# CHARGING_IC.net
KiCad netlist of a schematic drawn in Altium Designer
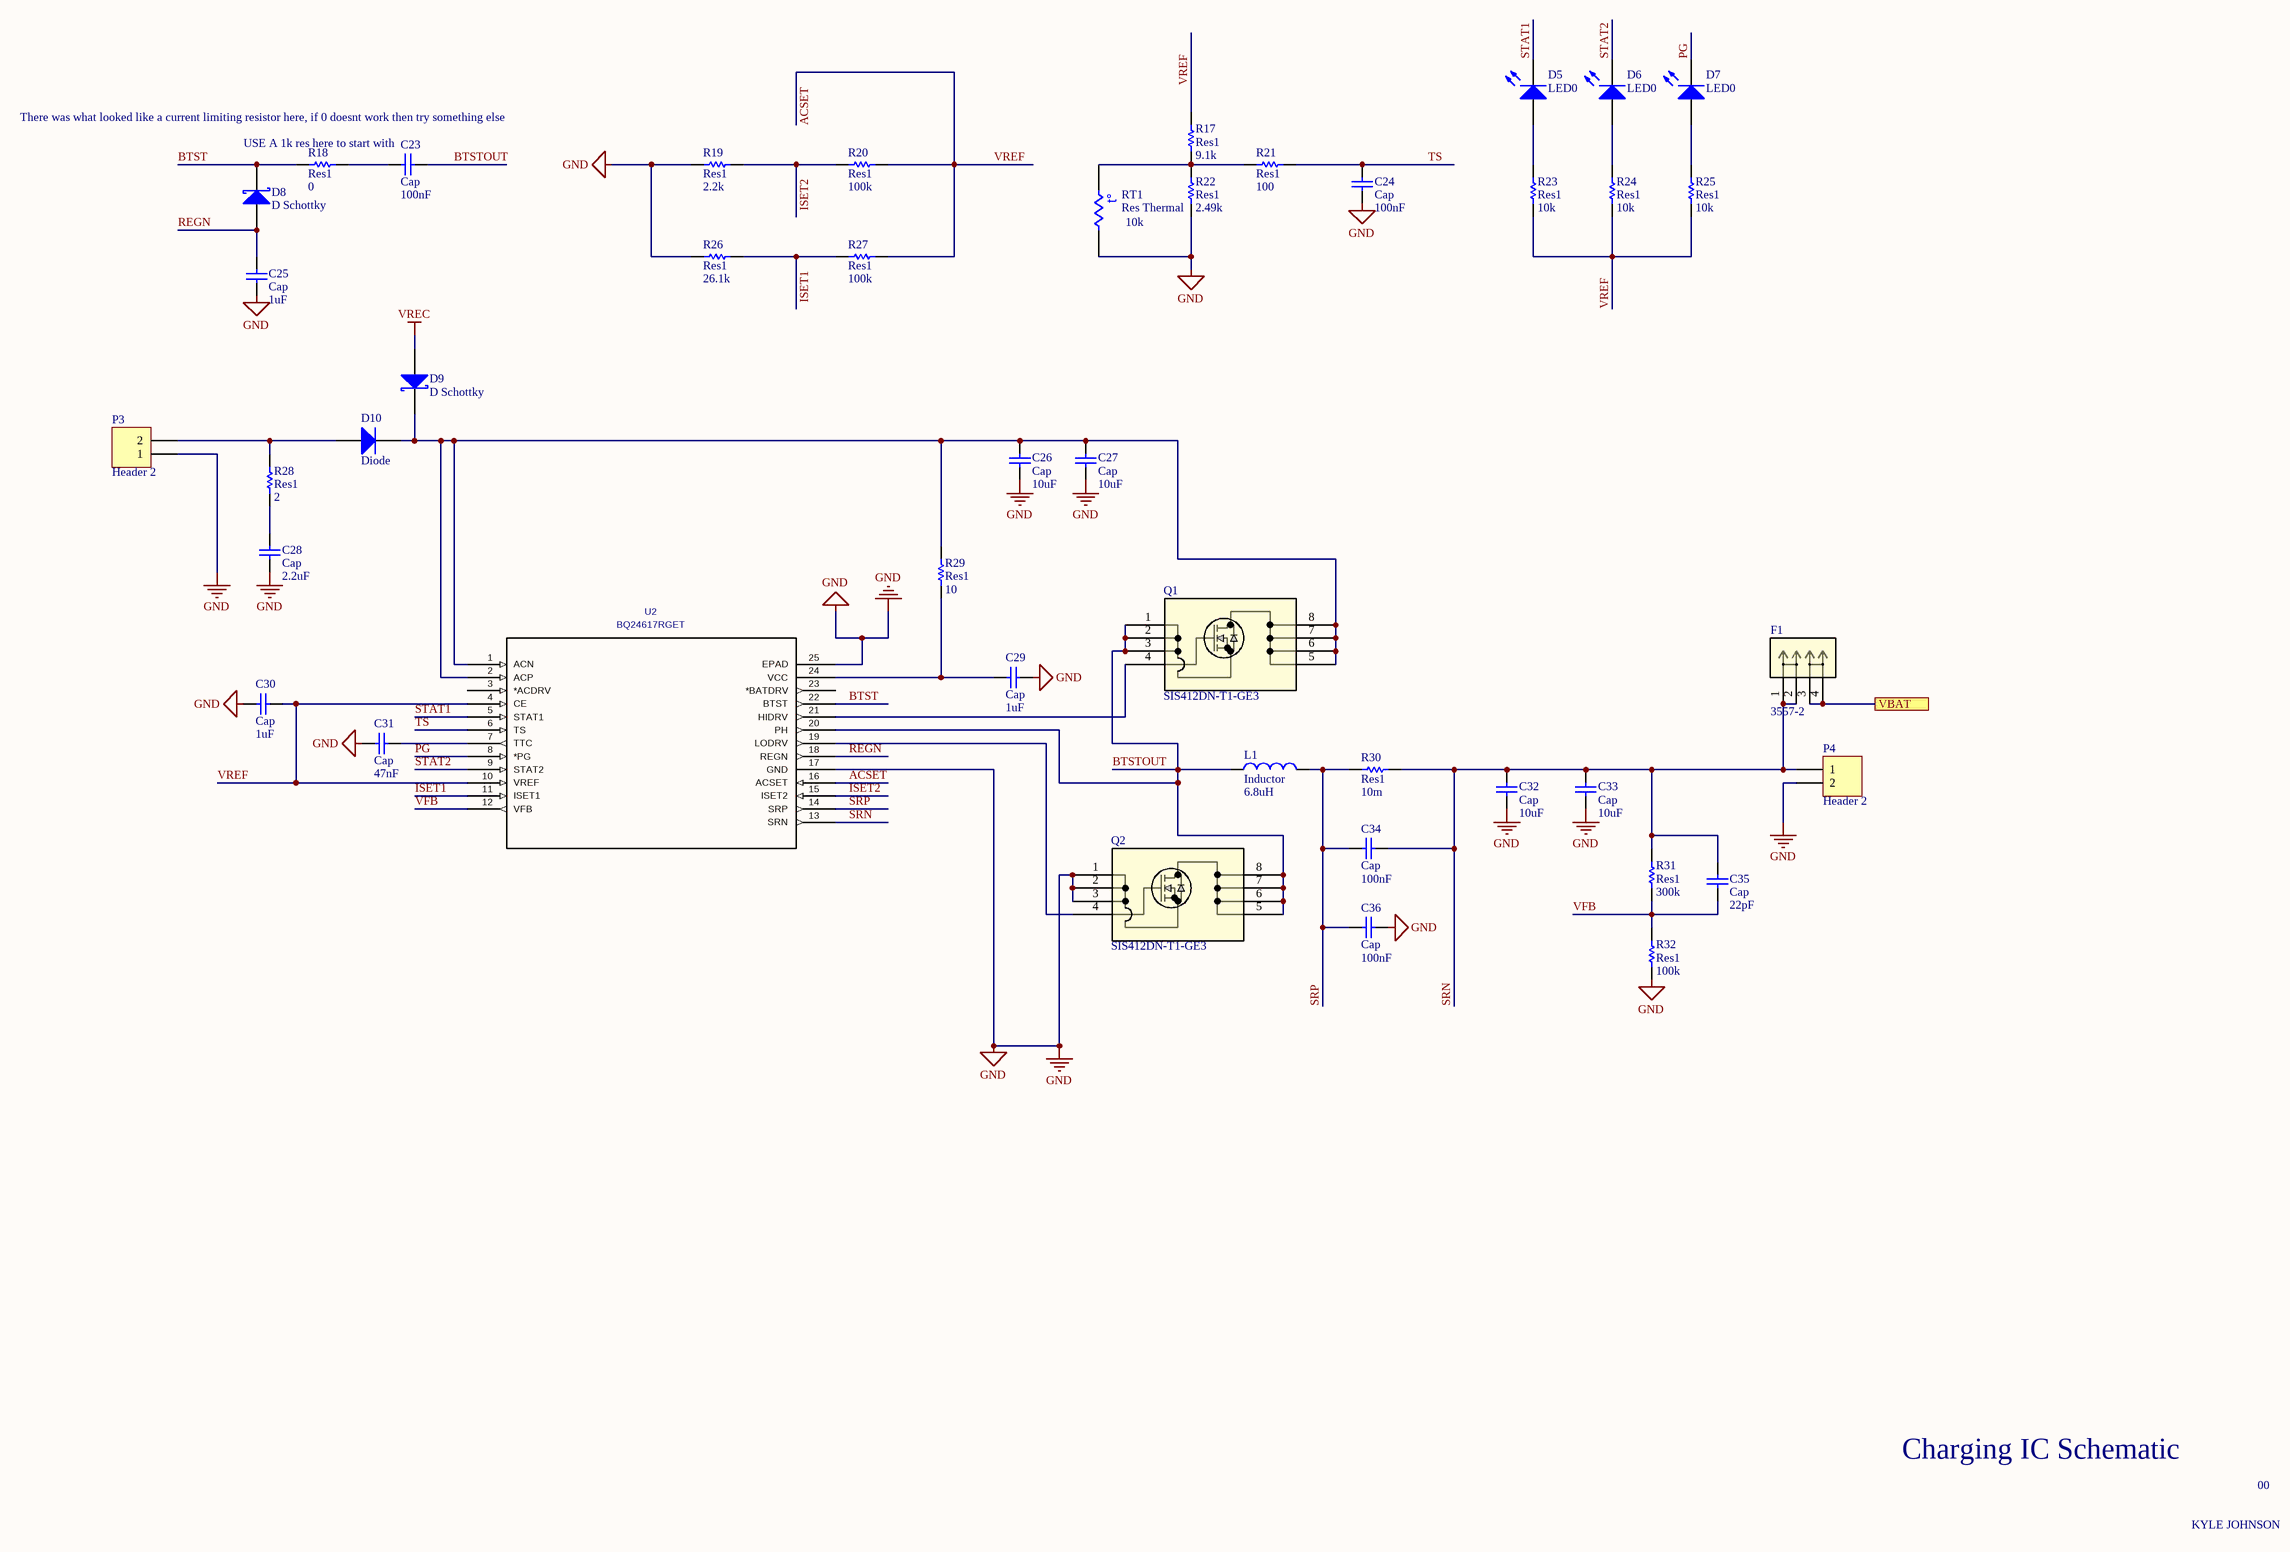
[diagram p0: CHARGING IC.SchDoc]

(export (version "E")
  (design (tool "Eeschema 10.0.6"))
  (components
    (comp (ref "C23")
      (value "Cap")
      (footprint "0402-A")
      (description "Capacitor")
      (fields (field (name "ALTIUM_VALUE") "100nF") (field (name "PUBLISHER") "Altium Limited"))
      (libsource (lib "Miscellaneous Devices") (part "Cap"))
    )
    (comp (ref "C24")
      (value "Cap")
      (footprint "0402-A")
      (description "Capacitor")
      (fields (field (name "ALTIUM_VALUE") "100nF") (field (name "PUBLISHER") "Altium Limited"))
      (libsource (lib "Miscellaneous Devices") (part "Cap"))
    )
    (comp (ref "C25")
      (value "Cap")
      (footprint "0402-A")
      (description "Capacitor")
      (fields (field (name "ALTIUM_VALUE") "1uF") (field (name "PUBLISHER") "Altium Limited"))
      (libsource (lib "Miscellaneous Devices") (part "Cap"))
    )
    (comp (ref "C26")
      (value "Cap")
      (footprint "6-0805_M")
      (description "Capacitor")
      (fields (field (name "ALTIUM_VALUE") "10uF") (field (name "PUBLISHER") "Altium Limited"))
      (libsource (lib "Miscellaneous Devices") (part "Cap"))
    )
    (comp (ref "C27")
      (value "Cap")
      (footprint "6-0805_M")
      (description "Capacitor")
      (fields (field (name "ALTIUM_VALUE") "10uF") (field (name "PUBLISHER") "Altium Limited"))
      (libsource (lib "Miscellaneous Devices") (part "Cap"))
    )
    (comp (ref "C28")
      (value "Cap")
      (footprint "1608[0603]")
      (description "Capacitor")
      (fields (field (name "ALTIUM_VALUE") "2.2uF") (field (name "PUBLISHER") "Altium Limited"))
      (libsource (lib "Miscellaneous Devices") (part "Cap"))
    )
    (comp (ref "C29")
      (value "Cap")
      (footprint "0402-A")
      (description "Capacitor")
      (fields (field (name "ALTIUM_VALUE") "1uF") (field (name "PUBLISHER") "Altium Limited"))
      (libsource (lib "Miscellaneous Devices") (part "Cap"))
    )
    (comp (ref "C30")
      (value "Cap")
      (footprint "0402-A")
      (description "Capacitor")
      (fields (field (name "ALTIUM_VALUE") "1uF") (field (name "PUBLISHER") "Altium Limited"))
      (libsource (lib "Miscellaneous Devices") (part "Cap"))
    )
    (comp (ref "C31")
      (value "Cap")
      (footprint "0402-A")
      (description "Capacitor")
      (fields (field (name "ALTIUM_VALUE") "47nF") (field (name "PUBLISHER") "Altium Limited"))
      (libsource (lib "Miscellaneous Devices") (part "Cap"))
    )
    (comp (ref "C32")
      (value "Cap")
      (footprint "6-0805_M")
      (description "Capacitor")
      (fields (field (name "ALTIUM_VALUE") "10uF") (field (name "PUBLISHER") "Altium Limited"))
      (libsource (lib "Miscellaneous Devices") (part "Cap"))
    )
    (comp (ref "C33")
      (value "Cap")
      (footprint "6-0805_M")
      (description "Capacitor")
      (fields (field (name "ALTIUM_VALUE") "10uF") (field (name "PUBLISHER") "Altium Limited"))
      (libsource (lib "Miscellaneous Devices") (part "Cap"))
    )
    (comp (ref "C34")
      (value "Cap")
      (footprint "0402-A")
      (description "Capacitor")
      (fields (field (name "ALTIUM_VALUE") "100nF") (field (name "PUBLISHER") "Altium Limited"))
      (libsource (lib "Miscellaneous Devices") (part "Cap"))
    )
    (comp (ref "C35")
      (value "Cap")
      (footprint "0402-A")
      (description "Capacitor")
      (fields (field (name "ALTIUM_VALUE") "22pF") (field (name "PUBLISHER") "Altium Limited"))
      (libsource (lib "Miscellaneous Devices") (part "Cap"))
    )
    (comp (ref "C36")
      (value "Cap")
      (footprint "0402-A")
      (description "Capacitor")
      (fields (field (name "ALTIUM_VALUE") "100nF") (field (name "PUBLISHER") "Altium Limited"))
      (libsource (lib "Miscellaneous Devices") (part "Cap"))
    )
    (comp (ref "D5")
      (value "LED0")
      (footprint "1608[0603]")
      (fields (field (name "PUBLISHER") "Altium Limited"))
      (libsource (lib "Miscellaneous Devices") (part "LED0"))
    )
    (comp (ref "D6")
      (value "LED0")
      (footprint "1608[0603]")
      (fields (field (name "PUBLISHER") "Altium Limited"))
      (libsource (lib "Miscellaneous Devices") (part "LED0"))
    )
    (comp (ref "D7")
      (value "LED0")
      (footprint "1608[0603]")
      (fields (field (name "PUBLISHER") "Altium Limited"))
      (libsource (lib "Miscellaneous Devices") (part "LED0"))
    )
    (comp (ref "D8")
      (value "D Schottky")
      (footprint "425")
      (description "Schottky Diode")
      (fields (field (name "PUBLISHER") "Altium Limited"))
      (libsource (lib "Miscellaneous Devices") (part "D Schottky"))
    )
    (comp (ref "D9")
      (value "D Schottky")
      (footprint "425")
      (description "Schottky Diode")
      (fields (field (name "PUBLISHER") "Altium Limited"))
      (libsource (lib "Miscellaneous Devices") (part "D Schottky"))
    )
    (comp (ref "D10")
      (value "Diode")
      (footprint "X3-WLB1608-2")
      (description "Default Diode")
      (fields (field (name "PUBLISHER") "Altium Limited"))
      (libsource (lib "Miscellaneous Devices") (part "Diode"))
    )
    (comp (ref "F1")
      (value "3557-2")
      (footprint "CONN_3557-2_KEY")
      (description "No Description Available")
      (fields (field (name "COPYRIGHT") "Copyright (C) 2018 Accelerated Designs. All rights reserved"))
      (libsource (lib "3557-2") (part "3557-2"))
    )
    (comp (ref "L1")
      (value "Inductor")
      (footprint "IHLP2525CZER6R8MA1")
      (fields (field (name "ALTIUM_VALUE") "6.8uH") (field (name "PUBLISHER") "Altium Limited"))
      (libsource (lib "Miscellaneous Devices") (part "Inductor"))
    )
    (comp (ref "P3")
      (value "Header 2")
      (footprint "2-1445096-2")
      (description "Header, 2-Pin")
      (fields (field (name "PUBLISHER") "Altium Limited"))
      (libsource (lib "") (part "Header 2_1"))
    )
    (comp (ref "P4")
      (value "Header 2")
      (footprint "2-1445096-2")
      (description "Header, 2-Pin")
      (fields (field (name "PUBLISHER") "Altium Limited"))
      (libsource (lib "Miscellaneous Connectors") (part "Header 2"))
    )
    (comp (ref "Q1")
      (value "SIS412DN-T1-GE3")
      (footprint "POWERPAK_1212-8")
      (description "No Description Available")
      (fields (field (name "COPYRIGHT") "Copyright (C) 2018 Accelerated Designs. All rights reserved"))
      (libsource (lib "SIS412DN-T1-GE3") (part "SIS412DN-T1-GE3"))
    )
    (comp (ref "Q2")
      (value "SIS412DN-T1-GE3")
      (footprint "POWERPAK_1212-8")
      (description "No Description Available")
      (fields (field (name "COPYRIGHT") "Copyright (C) 2018 Accelerated Designs. All rights reserved"))
      (libsource (lib "SIS412DN-T1-GE3") (part "SIS412DN-T1-GE3"))
    )
    (comp (ref "R17")
      (value "Res1")
      (footprint "0402-A")
      (description "Resistor")
      (fields (field (name "ALTIUM_VALUE") "9.1k") (field (name "PUBLISHER") "Altium Limited"))
      (libsource (lib "Miscellaneous Devices") (part "Res1"))
    )
    (comp (ref "R18")
      (value "Res1")
      (footprint "0402-A")
      (description "Resistor")
      (fields (field (name "ALTIUM_VALUE") "0") (field (name "PUBLISHER") "Altium Limited"))
      (libsource (lib "Miscellaneous Devices") (part "Res1"))
    )
    (comp (ref "R19")
      (value "Res1")
      (footprint "0402-A")
      (description "Resistor")
      (fields (field (name "ALTIUM_VALUE") "2.2k") (field (name "PUBLISHER") "Altium Limited"))
      (libsource (lib "Miscellaneous Devices") (part "Res1"))
    )
    (comp (ref "R20")
      (value "Res1")
      (footprint "0402-A")
      (description "Resistor")
      (fields (field (name "ALTIUM_VALUE") "100k") (field (name "PUBLISHER") "Altium Limited"))
      (libsource (lib "Miscellaneous Devices") (part "Res1"))
    )
    (comp (ref "R21")
      (value "Res1")
      (footprint "0402-A")
      (description "Resistor")
      (fields (field (name "ALTIUM_VALUE") "100") (field (name "PUBLISHER") "Altium Limited"))
      (libsource (lib "Miscellaneous Devices") (part "Res1"))
    )
    (comp (ref "R22")
      (value "Res1")
      (footprint "0402-A")
      (description "Resistor")
      (fields (field (name "ALTIUM_VALUE") "2.49k") (field (name "PUBLISHER") "Altium Limited"))
      (libsource (lib "Miscellaneous Devices") (part "Res1"))
    )
    (comp (ref "R23")
      (value "Res1")
      (footprint "0402-A")
      (description "Resistor")
      (fields (field (name "ALTIUM_VALUE") "10k") (field (name "PUBLISHER") "Altium Limited"))
      (libsource (lib "Miscellaneous Devices") (part "Res1"))
    )
    (comp (ref "R24")
      (value "Res1")
      (footprint "0402-A")
      (description "Resistor")
      (fields (field (name "ALTIUM_VALUE") "10k") (field (name "PUBLISHER") "Altium Limited"))
      (libsource (lib "Miscellaneous Devices") (part "Res1"))
    )
    (comp (ref "R25")
      (value "Res1")
      (footprint "0402-A")
      (description "Resistor")
      (fields (field (name "ALTIUM_VALUE") "10k") (field (name "PUBLISHER") "Altium Limited"))
      (libsource (lib "Miscellaneous Devices") (part "Res1"))
    )
    (comp (ref "R26")
      (value "Res1")
      (footprint "0402-A")
      (description "Resistor")
      (fields (field (name "ALTIUM_VALUE") "26.1k") (field (name "PUBLISHER") "Altium Limited"))
      (libsource (lib "Miscellaneous Devices") (part "Res1"))
    )
    (comp (ref "R27")
      (value "Res1")
      (footprint "0402-A")
      (description "Resistor")
      (fields (field (name "ALTIUM_VALUE") "100k") (field (name "PUBLISHER") "Altium Limited"))
      (libsource (lib "Miscellaneous Devices") (part "Res1"))
    )
    (comp (ref "R28")
      (value "Res1")
      (footprint "6-0805_M")
      (description "Resistor")
      (fields (field (name "ALTIUM_VALUE") "2") (field (name "PUBLISHER") "Altium Limited"))
      (libsource (lib "Miscellaneous Devices") (part "Res1"))
    )
    (comp (ref "R29")
      (value "Res1")
      (footprint "0402-A")
      (description "Resistor")
      (fields (field (name "ALTIUM_VALUE") "10") (field (name "PUBLISHER") "Altium Limited"))
      (libsource (lib "Miscellaneous Devices") (part "Res1"))
    )
    (comp (ref "R30")
      (value "Res1")
      (footprint "6-0805_M")
      (description "Resistor")
      (fields (field (name "ALTIUM_VALUE") "10m") (field (name "PUBLISHER") "Altium Limited"))
      (libsource (lib "Miscellaneous Devices") (part "Res1"))
    )
    (comp (ref "R31")
      (value "Res1")
      (footprint "0402-A")
      (description "Resistor")
      (fields (field (name "ALTIUM_VALUE") "300k") (field (name "PUBLISHER") "Altium Limited"))
      (libsource (lib "Miscellaneous Devices") (part "Res1"))
    )
    (comp (ref "R32")
      (value "Res1")
      (footprint "0402-A")
      (description "Resistor")
      (fields (field (name "ALTIUM_VALUE") "100k") (field (name "PUBLISHER") "Altium Limited"))
      (libsource (lib "Miscellaneous Devices") (part "Res1"))
    )
    (comp (ref "RT1")
      (value "Res Thermal")
      (footprint "1608[0603]")
      (description "Thermistor")
      (fields (field (name "ALTIUM_VALUE") "10k") (field (name "PUBLISHER") "Altium Limited"))
      (libsource (lib "Miscellaneous Devices") (part "Res Thermal"))
    )
    (comp (ref "U2")
      (value "BQ24617RGET")
      (footprint "RGE24_2P45X2P45")
      (fields (field (name "MANUFACTURER") "Texas Instruments"))
      (libsource (lib "BQ24617RGET") (part "BQ24617RGET"))
    )
  )
  (nets
    (net (code "1") (name "/ACSET") (class "Default")
      (node (ref "C30") (pin "1") (pinfunction "1_1") (pintype "passive"))
      (node (ref "R17") (pin "2") (pinfunction "2_2") (pintype "passive"))
      (node (ref "R20") (pin "2") (pinfunction "2_2") (pintype "passive"))
      (node (ref "R23") (pin "1") (pinfunction "1_1") (pintype "passive"))
      (node (ref "R24") (pin "1") (pinfunction "1_1") (pintype "passive"))
      (node (ref "R25") (pin "1") (pinfunction "1_1") (pintype "passive"))
      (node (ref "R27") (pin "2") (pinfunction "2_2") (pintype "passive"))
      (node (ref "U2") (pin "10") (pinfunction "VREF_10") (pintype "input"))
      (node (ref "U2") (pin "16") (pinfunction "ACSET_16") (pintype "input"))
      (node (ref "U2") (pin "4") (pinfunction "CE_4") (pintype "input"))
    )
    (net (code "2") (name "/BTST") (class "Default")
      (node (ref "D8") (pin "2") (pinfunction "K_2") (pintype "passive"))
      (node (ref "R18") (pin "1") (pinfunction "1_1") (pintype "passive"))
      (node (ref "U2") (pin "22") (pinfunction "BTST_22") (pintype "output"))
    )
    (net (code "3") (name "/BTSTOUT") (class "Default")
      (node (ref "C23") (pin "2") (pinfunction "2_2") (pintype "passive"))
      (node (ref "L1") (pin "1") (pinfunction "1_1") (pintype "passive"))
      (node (ref "Q1") (pin "1") (pinfunction "S_1") (pintype "passive"))
      (node (ref "Q1") (pin "2") (pinfunction "S_2") (pintype "passive"))
      (node (ref "Q1") (pin "3") (pinfunction "S_3") (pintype "passive"))
      (node (ref "Q2") (pin "5") (pinfunction "D_5") (pintype "passive"))
      (node (ref "Q2") (pin "6") (pinfunction "D_6") (pintype "passive"))
      (node (ref "Q2") (pin "7") (pinfunction "D_7") (pintype "passive"))
      (node (ref "Q2") (pin "8") (pinfunction "D_8") (pintype "passive"))
      (node (ref "U2") (pin "20") (pinfunction "PH_20") (pintype "output"))
    )
    (net (code "4") (name "/ISET1") (class "Default")
      (node (ref "R26") (pin "2") (pinfunction "2_2") (pintype "passive"))
      (node (ref "R27") (pin "1") (pinfunction "1_1") (pintype "passive"))
      (node (ref "U2") (pin "11") (pinfunction "ISET1_11") (pintype "input"))
    )
    (net (code "5") (name "/ISET2") (class "Default")
      (node (ref "R19") (pin "2") (pinfunction "2_2") (pintype "passive"))
      (node (ref "R20") (pin "1") (pinfunction "1_1") (pintype "passive"))
      (node (ref "U2") (pin "15") (pinfunction "ISET2_15") (pintype "input"))
    )
    (net (code "6") (name "/PG") (class "Default")
      (node (ref "D7") (pin "2") (pinfunction "K_2") (pintype "passive"))
      (node (ref "U2") (pin "8") (pinfunction "*PG_8") (pintype "input"))
    )
    (net (code "7") (name "/REGN") (class "Default")
      (node (ref "C25") (pin "2") (pinfunction "2_2") (pintype "passive"))
      (node (ref "D8") (pin "1") (pinfunction "A_1") (pintype "passive"))
      (node (ref "U2") (pin "18") (pinfunction "REGN_18") (pintype "output"))
    )
    (net (code "8") (name "/SRN") (class "Default")
      (node (ref "C32") (pin "2") (pinfunction "2_2") (pintype "passive"))
      (node (ref "C33") (pin "2") (pinfunction "2_2") (pintype "passive"))
      (node (ref "C34") (pin "1") (pinfunction "1_1") (pintype "passive"))
      (node (ref "C35") (pin "1") (pinfunction "1_1") (pintype "passive"))
      (node (ref "F1") (pin "1") (pinfunction "1_1") (pintype "passive"))
      (node (ref "F1") (pin "2") (pinfunction "2_2") (pintype "passive"))
      (node (ref "P4") (pin "1") (pinfunction "1_1") (pintype "passive"))
      (node (ref "R30") (pin "2") (pinfunction "2_2") (pintype "passive"))
      (node (ref "R31") (pin "2") (pinfunction "2_2") (pintype "passive"))
      (node (ref "U2") (pin "13") (pinfunction "SRN_13") (pintype "output"))
    )
    (net (code "9") (name "/SRP") (class "Default")
      (node (ref "C34") (pin "2") (pinfunction "2_2") (pintype "passive"))
      (node (ref "C36") (pin "1") (pinfunction "1_1") (pintype "passive"))
      (node (ref "L1") (pin "2") (pinfunction "2_2") (pintype "passive"))
      (node (ref "R30") (pin "1") (pinfunction "1_1") (pintype "passive"))
      (node (ref "U2") (pin "14") (pinfunction "SRP_14") (pintype "output"))
    )
    (net (code "10") (name "/STAT1") (class "Default")
      (node (ref "D5") (pin "2") (pinfunction "K_2") (pintype "passive"))
      (node (ref "U2") (pin "5") (pinfunction "STAT1_5") (pintype "input"))
    )
    (net (code "11") (name "/STAT2") (class "Default")
      (node (ref "D6") (pin "2") (pinfunction "K_2") (pintype "passive"))
      (node (ref "U2") (pin "9") (pinfunction "STAT2_9") (pintype "input"))
    )
    (net (code "12") (name "/TS") (class "Default")
      (node (ref "C24") (pin "2") (pinfunction "2_2") (pintype "passive"))
      (node (ref "R21") (pin "2") (pinfunction "2_2") (pintype "passive"))
      (node (ref "U2") (pin "6") (pinfunction "TS_6") (pintype "input"))
    )
    (net (code "13") (name "/VBAT") (class "Default")
      (node (ref "F1") (pin "3") (pinfunction "3_3") (pintype "passive"))
      (node (ref "F1") (pin "4") (pinfunction "4_4") (pintype "passive"))
    )
    (net (code "14") (name "/VFB") (class "Default")
      (node (ref "C35") (pin "2") (pinfunction "2_2") (pintype "passive"))
      (node (ref "R31") (pin "1") (pinfunction "1_1") (pintype "passive"))
      (node (ref "R32") (pin "2") (pinfunction "2_2") (pintype "passive"))
      (node (ref "U2") (pin "12") (pinfunction "VFB_12") (pintype "output"))
    )
    (net (code "15") (name "GND") (class "Default")
      (node (ref "C24") (pin "1") (pinfunction "1_1") (pintype "passive"))
      (node (ref "C25") (pin "1") (pinfunction "1_1") (pintype "passive"))
      (node (ref "C26") (pin "1") (pinfunction "1_1") (pintype "passive"))
      (node (ref "C27") (pin "1") (pinfunction "1_1") (pintype "passive"))
      (node (ref "C28") (pin "1") (pinfunction "1_1") (pintype "passive"))
      (node (ref "C29") (pin "2") (pinfunction "2_2") (pintype "passive"))
      (node (ref "C30") (pin "2") (pinfunction "2_2") (pintype "passive"))
      (node (ref "C31") (pin "1") (pinfunction "1_1") (pintype "passive"))
      (node (ref "C32") (pin "1") (pinfunction "1_1") (pintype "passive"))
      (node (ref "C33") (pin "1") (pinfunction "1_1") (pintype "passive"))
      (node (ref "C36") (pin "2") (pinfunction "2_2") (pintype "passive"))
      (node (ref "P3") (pin "1") (pinfunction "1_1") (pintype "passive"))
      (node (ref "P4") (pin "2") (pinfunction "2_2") (pintype "passive"))
      (node (ref "Q2") (pin "1") (pinfunction "S_1") (pintype "passive"))
      (node (ref "Q2") (pin "2") (pinfunction "S_2") (pintype "passive"))
      (node (ref "Q2") (pin "3") (pinfunction "S_3") (pintype "passive"))
      (node (ref "R19") (pin "1") (pinfunction "1_1") (pintype "passive"))
      (node (ref "R22") (pin "1") (pinfunction "1_1") (pintype "passive"))
      (node (ref "R26") (pin "1") (pinfunction "1_1") (pintype "passive"))
      (node (ref "R32") (pin "1") (pinfunction "1_1") (pintype "passive"))
      (node (ref "RT1") (pin "2") (pinfunction "2_2") (pintype "passive"))
      (node (ref "U2") (pin "17") (pinfunction "GND_17") (pintype "power_in"))
      (node (ref "U2") (pin "25") (pinfunction "EPAD_25") (pintype "power_in"))
    )
    (net (code "16") (name "Net-(C23-Pad1)") (class "Default")
      (node (ref "C23") (pin "1") (pinfunction "1_1") (pintype "passive"))
      (node (ref "R18") (pin "2") (pinfunction "2_2") (pintype "passive"))
    )
    (net (code "17") (name "Net-(C28-Pad2)") (class "Default")
      (node (ref "C28") (pin "2") (pinfunction "2_2") (pintype "passive"))
      (node (ref "R28") (pin "1") (pinfunction "1_1") (pintype "passive"))
    )
    (net (code "18") (name "Net-(D5-A)") (class "Default")
      (node (ref "D5") (pin "1") (pinfunction "A_1") (pintype "passive"))
      (node (ref "R23") (pin "2") (pinfunction "2_2") (pintype "passive"))
    )
    (net (code "19") (name "Net-(D6-A)") (class "Default")
      (node (ref "D6") (pin "1") (pinfunction "A_1") (pintype "passive"))
      (node (ref "R24") (pin "2") (pinfunction "2_2") (pintype "passive"))
    )
    (net (code "20") (name "Net-(D7-A)") (class "Default")
      (node (ref "D7") (pin "1") (pinfunction "A_1") (pintype "passive"))
      (node (ref "R25") (pin "2") (pinfunction "2_2") (pintype "passive"))
    )
    (net (code "21") (name "Net-(D10-A)") (class "Default")
      (node (ref "D10") (pin "1") (pinfunction "A_1") (pintype "passive"))
      (node (ref "P3") (pin "2") (pinfunction "2_2") (pintype "passive"))
      (node (ref "R28") (pin "2") (pinfunction "2_2") (pintype "passive"))
    )
    (net (code "22") (name "Net-(D10-K)") (class "Default")
      (node (ref "C26") (pin "2") (pinfunction "2_2") (pintype "passive"))
      (node (ref "C27") (pin "2") (pinfunction "2_2") (pintype "passive"))
      (node (ref "D10") (pin "2") (pinfunction "K_2") (pintype "passive"))
      (node (ref "D9") (pin "2") (pinfunction "K_2") (pintype "passive"))
      (node (ref "Q1") (pin "5") (pinfunction "D_5") (pintype "passive"))
      (node (ref "Q1") (pin "6") (pinfunction "D_6") (pintype "passive"))
      (node (ref "Q1") (pin "7") (pinfunction "D_7") (pintype "passive"))
      (node (ref "Q1") (pin "8") (pinfunction "D_8") (pintype "passive"))
      (node (ref "R29") (pin "2") (pinfunction "2_2") (pintype "passive"))
      (node (ref "U2") (pin "1") (pinfunction "ACN_1") (pintype "input"))
      (node (ref "U2") (pin "2") (pinfunction "ACP_2") (pintype "input"))
    )
    (net (code "23") (name "Net-(Q1-G)") (class "Default")
      (node (ref "Q1") (pin "4") (pinfunction "G_4") (pintype "passive"))
      (node (ref "U2") (pin "21") (pinfunction "HIDRV_21") (pintype "output"))
    )
    (net (code "24") (name "Net-(Q2-G)") (class "Default")
      (node (ref "Q2") (pin "4") (pinfunction "G_4") (pintype "passive"))
      (node (ref "U2") (pin "19") (pinfunction "LODRV_19") (pintype "output"))
    )
    (net (code "25") (name "Net-(R17-Pad1)") (class "Default")
      (node (ref "R17") (pin "1") (pinfunction "1_1") (pintype "passive"))
      (node (ref "R21") (pin "1") (pinfunction "1_1") (pintype "passive"))
      (node (ref "R22") (pin "2") (pinfunction "2_2") (pintype "passive"))
      (node (ref "RT1") (pin "1") (pinfunction "1_1") (pintype "passive"))
    )
    (net (code "26") (name "Net-(U2-TTC)") (class "Default")
      (node (ref "C31") (pin "2") (pinfunction "2_2") (pintype "passive"))
      (node (ref "U2") (pin "7") (pinfunction "TTC_7") (pintype "output"))
    )
    (net (code "27") (name "Net-(U2-VCC)") (class "Default")
      (node (ref "C29") (pin "1") (pinfunction "1_1") (pintype "passive"))
      (node (ref "R29") (pin "1") (pinfunction "1_1") (pintype "passive"))
      (node (ref "U2") (pin "24") (pinfunction "VCC_24") (pintype "power_in"))
    )
    (net (code "28") (name "VREC") (class "Default")
      (node (ref "D9") (pin "1") (pinfunction "A_1") (pintype "passive"))
    )
    (net (code "29") (name "unconnected-(U2-*ACDRV-Pad3)") (class "Default")
      (node (ref "U2") (pin "3") (pinfunction "*ACDRV_3") (pintype "input"))
    )
    (net (code "30") (name "unconnected-(U2-*BATDRV-Pad23)") (class "Default")
      (node (ref "U2") (pin "23") (pinfunction "*BATDRV_23") (pintype "output"))
    )
  )
)
